# board.net
KiCad netlist of a schematic drawn in EAGLE
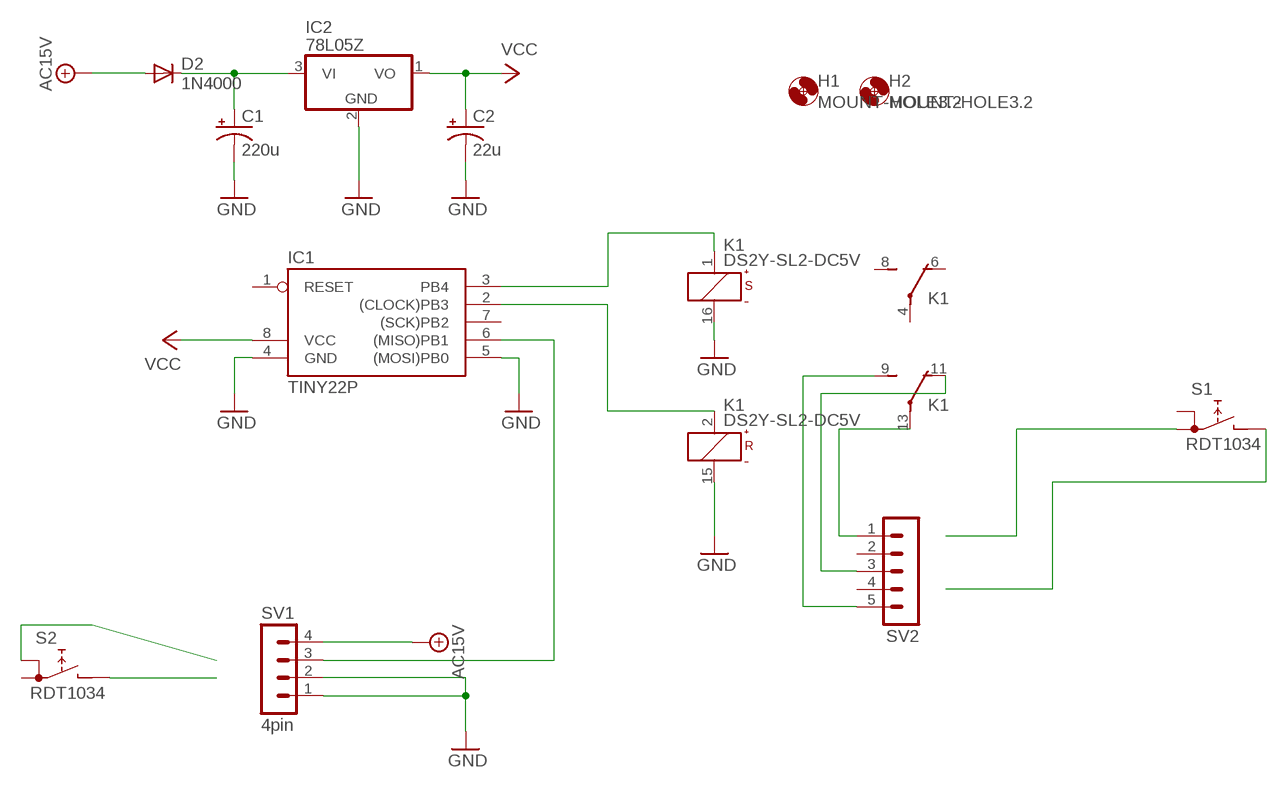
[diagram p0: schematic, sheet 1]

(export (version "E")
  (design (tool "Eeschema 10.0.6"))
  (components
    (comp (ref "C1")
      (value "220u")
      (footprint "eagle-import:E5-10,5")
      (libsource (lib "eagle-import") (part "CPOL-USE5-10.5"))
    )
    (comp (ref "C2")
      (value "22u")
      (footprint "eagle-import:E5-10,5")
      (libsource (lib "eagle-import") (part "CPOL-USE5-10.5"))
    )
    (comp (ref "D2")
      (value "1N4000")
      (footprint "eagle-import:D-12.5")
      (libsource (lib "eagle-import") (part "DIODE-D-12.5"))
    )
    (comp (ref "H1")
      (value "MOUNT-HOLE3.2")
      (footprint "eagle-import:3,2")
      (libsource (lib "eagle-import") (part "MOUNT-HOLE3.2"))
    )
    (comp (ref "H2")
      (value "MOUNT-HOLE3.2")
      (footprint "eagle-import:3,2")
      (libsource (lib "eagle-import") (part "MOUNT-HOLE3.2"))
    )
    (comp (ref "IC1")
      (value "TINY22P")
      (footprint "eagle-import:DIL08")
      (libsource (lib "eagle-import") (part "TINY22P"))
    )
    (comp (ref "IC2")
      (value "78L05Z")
      (footprint "eagle-import:TO92")
      (libsource (lib "eagle-import") (part "78ZL05"))
    )
    (comp (ref "K1")
      (value "DS2Y-SL2-DC5V")
      (footprint "eagle-import:DS2Y-2")
      (fields (field (name "MF") "AROMAT/ MATSUSHITA"))
      (libsource (lib "eagle-import") (part "DS2Y-SL2-DC5V"))
    )
    (comp (ref "S1")
      (value "RDT1034")
      (footprint "eagle-import:RDT1034")
      (libsource (lib "eagle-import") (part "RDT1034"))
    )
    (comp (ref "S2")
      (value "RDT1034")
      (footprint "eagle-import:RDT1034")
      (libsource (lib "eagle-import") (part "RDT1034"))
    )
    (comp (ref "SV1")
      (value "4pin")
      (footprint "eagle-import:MA04-1")
      (libsource (lib "eagle-import") (part "MA04-1"))
    )
    (comp (ref "SV2")
      (value "MA05-1")
      (footprint "eagle-import:MA05-1")
      (libsource (lib "eagle-import") (part "MA05-1"))
    )
  )
  (nets
    (net (code "1") (name "AC15V") (class "Default")
      (node (ref "D2") (pin "A") (pinfunction "A_A") (pintype "passive"))
      (node (ref "SV1") (pin "4") (pinfunction "4_4") (pintype "passive"))
    )
    (net (code "2") (name "GND") (class "Default")
      (node (ref "C1") (pin "-") (pinfunction "-_-") (pintype "passive"))
      (node (ref "C2") (pin "-") (pinfunction "-_-") (pintype "passive"))
      (node (ref "IC1") (pin "4") (pinfunction "GND_4") (pintype "power_in"))
      (node (ref "IC1") (pin "5") (pinfunction "(MOSI)PB0_5") (pintype "bidirectional"))
      (node (ref "IC2") (pin "2") (pinfunction "GND_2") (pintype "passive"))
      (node (ref "K1") (pin "15") (pinfunction "-_15") (pintype "passive"))
      (node (ref "K1") (pin "16") (pinfunction "-_16") (pintype "passive"))
      (node (ref "SV1") (pin "1") (pinfunction "1_1") (pintype "passive"))
      (node (ref "SV1") (pin "2") (pinfunction "2_2") (pintype "passive"))
    )
    (net (code "3") (name "Net-(IC1-(CLOCK)PB3)") (class "Default")
      (node (ref "IC1") (pin "2") (pinfunction "(CLOCK)PB3_2") (pintype "bidirectional"))
      (node (ref "K1") (pin "2") (pinfunction "+_2") (pintype "passive"))
    )
    (net (code "4") (name "Net-(IC1-(MISO)PB1)") (class "Default")
      (node (ref "IC1") (pin "6") (pinfunction "(MISO)PB1_6") (pintype "bidirectional"))
      (node (ref "SV1") (pin "3") (pinfunction "3_3") (pintype "passive"))
    )
    (net (code "5") (name "Net-(IC1-PB4)") (class "Default")
      (node (ref "IC1") (pin "3") (pinfunction "PB4_3") (pintype "bidirectional"))
      (node (ref "K1") (pin "1") (pinfunction "+_1") (pintype "passive"))
    )
    (net (code "6") (name "Net-(IC2-VI)") (class "Default")
      (node (ref "C1") (pin "+") (pinfunction "+_+") (pintype "passive"))
      (node (ref "D2") (pin "C") (pinfunction "C_C") (pintype "passive"))
      (node (ref "IC2") (pin "3") (pinfunction "VI_3") (pintype "input"))
    )
    (net (code "7") (name "Net-(K1B-O)") (class "Default")
      (node (ref "K1") (pin "11") (pinfunction "O_11") (pintype "passive"))
      (node (ref "SV2") (pin "3") (pinfunction "3_3") (pintype "passive"))
    )
    (net (code "8") (name "Net-(K1B-P)") (class "Default")
      (node (ref "K1") (pin "13") (pinfunction "P_13") (pintype "passive"))
      (node (ref "SV2") (pin "1") (pinfunction "1_1") (pintype "passive"))
    )
    (net (code "9") (name "Net-(K1B-S)") (class "Default")
      (node (ref "K1") (pin "9") (pinfunction "S_9") (pintype "passive"))
      (node (ref "SV2") (pin "5") (pinfunction "5_5") (pintype "passive"))
    )
    (net (code "10") (name "VCC") (class "Default")
      (node (ref "C2") (pin "+") (pinfunction "+_+") (pintype "passive"))
      (node (ref "IC1") (pin "8") (pinfunction "VCC_8") (pintype "power_in"))
      (node (ref "IC2") (pin "1") (pinfunction "VO_1") (pintype "passive"))
    )
    (net (code "11") (name "unconnected-(IC1-(SCK)PB2-Pad7)") (class "Default")
      (node (ref "IC1") (pin "7") (pinfunction "(SCK)PB2_7") (pintype "bidirectional"))
    )
    (net (code "12") (name "unconnected-(IC1-RESET-Pad1)") (class "Default")
      (node (ref "IC1") (pin "1") (pinfunction "RESET_1") (pintype "input"))
    )
    (net (code "13") (name "unconnected-(K1A-O-Pad6)") (class "Default")
      (node (ref "K1") (pin "6") (pinfunction "O_6") (pintype "passive"))
    )
    (net (code "14") (name "unconnected-(K1A-P-Pad4)") (class "Default")
      (node (ref "K1") (pin "4") (pinfunction "P_4") (pintype "passive"))
    )
    (net (code "15") (name "unconnected-(K1A-S-Pad8)") (class "Default")
      (node (ref "K1") (pin "8") (pinfunction "S_8") (pintype "passive"))
    )
    (net (code "16") (name "unconnected-(S1-PadA)") (class "Default")
      (node (ref "S1") (pin "A") (pinfunction "A_A") (pintype "passive"))
    )
    (net (code "17") (name "unconnected-(S1-PadA1)") (class "Default")
      (node (ref "S1") (pin "A1") (pinfunction "A1_A1") (pintype "passive"))
    )
    (net (code "18") (name "unconnected-(S1-PadB)") (class "Default")
      (node (ref "S1") (pin "B") (pinfunction "B_B") (pintype "passive"))
    )
    (net (code "19") (name "unconnected-(S2-PadA)") (class "Default")
      (node (ref "S2") (pin "A") (pinfunction "A_A") (pintype "passive"))
    )
    (net (code "20") (name "unconnected-(S2-PadA1)") (class "Default")
      (node (ref "S2") (pin "A1") (pinfunction "A1_A1") (pintype "passive"))
    )
    (net (code "21") (name "unconnected-(S2-PadB)") (class "Default")
      (node (ref "S2") (pin "B") (pinfunction "B_B") (pintype "passive"))
    )
    (net (code "22") (name "unconnected-(SV2-Pad2)") (class "Default")
      (node (ref "SV2") (pin "2") (pinfunction "2_2") (pintype "passive"))
    )
    (net (code "23") (name "unconnected-(SV2-Pad4)") (class "Default")
      (node (ref "SV2") (pin "4") (pinfunction "4_4") (pintype "passive"))
    )
  )
)
